# SCH_555.net
KiCad netlist of a schematic drawn in Altium Designer
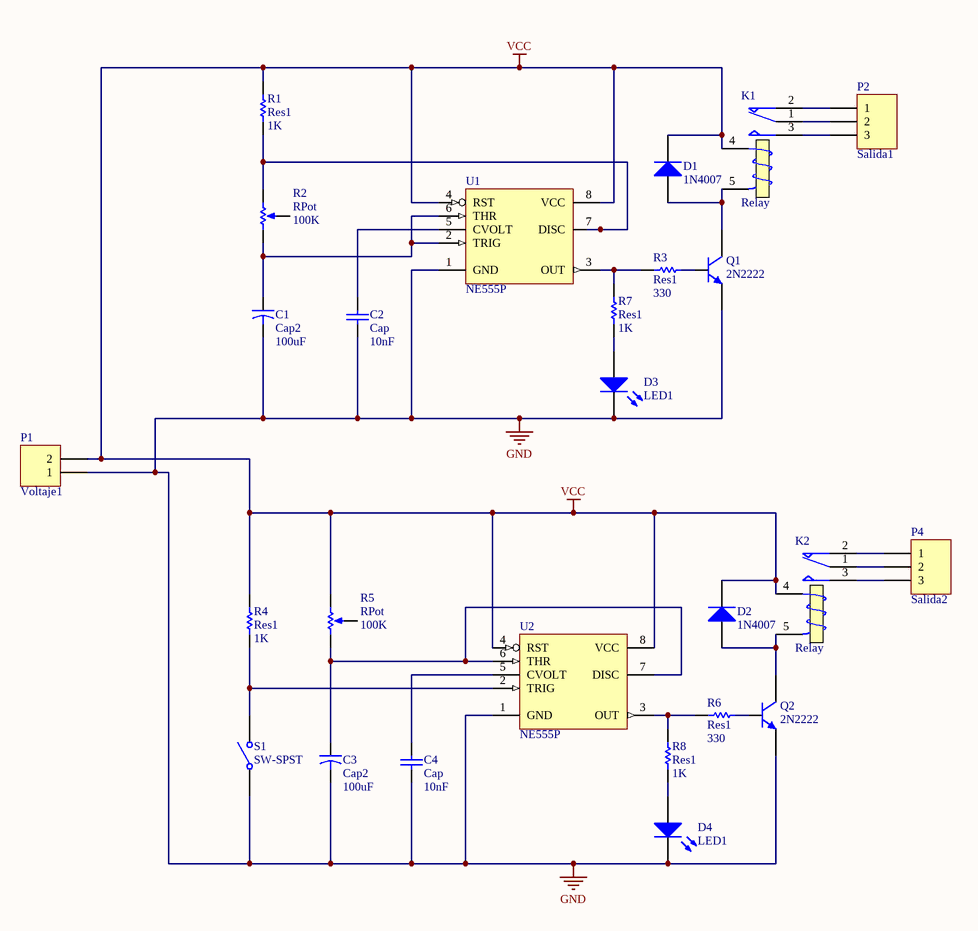
[diagram p0: SCH_555.SchDoc]

(export (version "E")
  (design (tool "Eeschema 10.0.6"))
  (components
    (comp (ref "C1")
      (value "Cap2")
      (footprint "Cap 100uf 25v")
      (description "Capacitor")
      (fields (field (name "ALTIUM_VALUE") "100uF") (field (name "PUBLISHER") "Altium Limited"))
      (libsource (lib "Miscellaneous Devices") (part "Cap2"))
    )
    (comp (ref "C2")
      (value "Cap")
      (footprint "CAP")
      (description "Capacitor")
      (fields (field (name "ALTIUM_VALUE") "10nF") (field (name "PUBLISHER") "Altium Limited"))
      (libsource (lib "Miscellaneous Devices") (part "Cap"))
    )
    (comp (ref "C3")
      (value "Cap2")
      (footprint "Cap 100uf 25v")
      (description "Capacitor")
      (fields (field (name "ALTIUM_VALUE") "100uF") (field (name "PUBLISHER") "Altium Limited"))
      (libsource (lib "Miscellaneous Devices") (part "Cap2"))
    )
    (comp (ref "C4")
      (value "Cap")
      (footprint "CAP")
      (description "Capacitor")
      (fields (field (name "ALTIUM_VALUE") "10nF") (field (name "PUBLISHER") "Altium Limited"))
      (libsource (lib "Miscellaneous Devices") (part "Cap"))
    )
    (comp (ref "D1")
      (value "1N4007")
      (footprint "DO-41")
      (description "1 Amp General Purpose Rectifier")
      (fields (field (name "PUBLISHER") "Altium Limited"))
      (libsource (lib "Miscellaneous Devices") (part "Diode 1N4007"))
    )
    (comp (ref "D2")
      (value "1N4007")
      (footprint "DO-41")
      (description "1 Amp General Purpose Rectifier")
      (fields (field (name "PUBLISHER") "Altium Limited"))
      (libsource (lib "Miscellaneous Devices") (part "Diode 1N4007"))
    )
    (comp (ref "D3")
      (value "LED1")
      (footprint "Cap 100uf 25v")
      (description "Typical RED GaAs LED")
      (fields (field (name "PUBLISHER") "Altium Limited"))
      (libsource (lib "Miscellaneous Devices") (part "LED1"))
    )
    (comp (ref "D4")
      (value "LED1")
      (footprint "Cap 100uf 25v")
      (description "Typical RED GaAs LED")
      (fields (field (name "PUBLISHER") "Altium Limited"))
      (libsource (lib "Miscellaneous Devices") (part "LED1"))
    )
    (comp (ref "K1")
      (value "Relay")
      (footprint "Relay")
      (description "SPDT Relay")
      (fields (field (name "PUBLISHER") "Altium Limited"))
      (libsource (lib "Miscellaneous Devices") (part "Relay"))
    )
    (comp (ref "K2")
      (value "Relay")
      (footprint "Relay")
      (description "SPDT Relay")
      (fields (field (name "PUBLISHER") "Altium Limited"))
      (libsource (lib "Miscellaneous Devices") (part "Relay"))
    )
    (comp (ref "P1")
      (value "Voltaje1")
      (footprint "TErminal")
      (description "Header, 2-Pin")
      (fields (field (name "PUBLISHER") "Altium Limited"))
      (libsource (lib "Miscellaneous Connectors") (part "Header 2"))
    )
    (comp (ref "P2")
      (value "Salida1")
      (footprint "TErminal3")
      (description "Header, 3-Pin")
      (fields (field (name "PUBLISHER") "Altium Limited"))
      (libsource (lib "Miscellaneous Connectors") (part "Header 3"))
    )
    (comp (ref "P4")
      (value "Salida2")
      (footprint "TErminal3")
      (description "Header, 3-Pin")
      (fields (field (name "PUBLISHER") "Altium Limited"))
      (libsource (lib "Miscellaneous Connectors") (part "Header 3"))
    )
    (comp (ref "Q1")
      (value "2N2222")
      (footprint "TO-92A")
      (description "NPN General Purpose Amplifier")
      (fields (field (name "PUBLISHER") "Altium Limited"))
      (libsource (lib "Miscellaneous Devices") (part "2N3904"))
    )
    (comp (ref "Q2")
      (value "2N2222")
      (footprint "TO-92A")
      (description "NPN General Purpose Amplifier")
      (fields (field (name "PUBLISHER") "Altium Limited"))
      (libsource (lib "Miscellaneous Devices") (part "2N3904"))
    )
    (comp (ref "R1")
      (value "Res1")
      (footprint "AXIAL-0.3")
      (description "Resistor")
      (fields (field (name "ALTIUM_VALUE") "1K") (field (name "PUBLISHER") "Altium Limited"))
      (libsource (lib "Miscellaneous Devices") (part "Res1"))
    )
    (comp (ref "R2")
      (value "RPot")
      (footprint "Potenciometro")
      (description "Potentiometer")
      (fields (field (name "ALTIUM_VALUE") "100K") (field (name "PUBLISHER") "Altium Limited"))
      (libsource (lib "Miscellaneous Devices") (part "RPot"))
    )
    (comp (ref "R3")
      (value "Res1")
      (footprint "AXIAL-0.3")
      (description "Resistor")
      (fields (field (name "ALTIUM_VALUE") "330") (field (name "PUBLISHER") "Altium Limited"))
      (libsource (lib "Miscellaneous Devices") (part "Res1"))
    )
    (comp (ref "R4")
      (value "Res1")
      (footprint "AXIAL-0.3")
      (description "Resistor")
      (fields (field (name "ALTIUM_VALUE") "1K") (field (name "PUBLISHER") "Altium Limited"))
      (libsource (lib "Miscellaneous Devices") (part "Res1"))
    )
    (comp (ref "R5")
      (value "RPot")
      (footprint "Potenciometro")
      (description "Potentiometer")
      (fields (field (name "ALTIUM_VALUE") "100K") (field (name "PUBLISHER") "Altium Limited"))
      (libsource (lib "Miscellaneous Devices") (part "RPot"))
    )
    (comp (ref "R6")
      (value "Res1")
      (footprint "AXIAL-0.3")
      (description "Resistor")
      (fields (field (name "ALTIUM_VALUE") "330") (field (name "PUBLISHER") "Altium Limited"))
      (libsource (lib "Miscellaneous Devices") (part "Res1"))
    )
    (comp (ref "R7")
      (value "Res1")
      (footprint "AXIAL-0.3")
      (description "Resistor")
      (fields (field (name "ALTIUM_VALUE") "1K") (field (name "PUBLISHER") "Altium Limited"))
      (libsource (lib "Miscellaneous Devices") (part "Res1"))
    )
    (comp (ref "R8")
      (value "Res1")
      (footprint "AXIAL-0.3")
      (description "Resistor")
      (fields (field (name "ALTIUM_VALUE") "1K") (field (name "PUBLISHER") "Altium Limited"))
      (libsource (lib "Miscellaneous Devices") (part "Res1"))
    )
    (comp (ref "S1")
      (value "SW-SPST")
      (footprint "PUSHB")
      (description "Single-Pole, Single-Throw Switch")
      (fields (field (name "PUBLISHER") "Altium Limited"))
      (libsource (lib "Miscellaneous Devices") (part "SW-SPST"))
    )
    (comp (ref "U1")
      (value "NE555P")
      (footprint "P008")
      (description "Precision Timer")
      (fields (field (name "PUBLISHER") "Altium Limited"))
      (libsource (lib "TI Analog Timer Circuit") (part "NE555P"))
    )
    (comp (ref "U2")
      (value "NE555P")
      (footprint "P008")
      (description "Precision Timer")
      (fields (field (name "PUBLISHER") "Altium Limited"))
      (libsource (lib "TI Analog Timer Circuit") (part "NE555P"))
    )
  )
  (nets
    (net (code "1") (name "GND") (class "Default")
      (node (ref "C1") (pin "2") (pinfunction "2_2") (pintype "passive"))
      (node (ref "C2") (pin "1") (pinfunction "1_1") (pintype "passive"))
      (node (ref "C3") (pin "2") (pinfunction "2_2") (pintype "passive"))
      (node (ref "C4") (pin "1") (pinfunction "1_1") (pintype "passive"))
      (node (ref "D3") (pin "2") (pinfunction "K_2") (pintype "passive"))
      (node (ref "D4") (pin "2") (pinfunction "K_2") (pintype "passive"))
      (node (ref "P1") (pin "1") (pinfunction "1_1") (pintype "passive"))
      (node (ref "Q1") (pin "1") (pinfunction "E_1") (pintype "passive"))
      (node (ref "Q2") (pin "1") (pinfunction "E_1") (pintype "passive"))
      (node (ref "S1") (pin "1") (pinfunction "COMMON_1") (pintype "passive"))
      (node (ref "U1") (pin "1") (pinfunction "GND_1") (pintype "power_in"))
      (node (ref "U2") (pin "1") (pinfunction "GND_1") (pintype "power_in"))
    )
    (net (code "2") (name "Net-(D1-A)") (class "Default")
      (node (ref "D1") (pin "1") (pinfunction "A_1") (pintype "passive"))
      (node (ref "K1") (pin "5") (pinfunction "T2_5") (pintype "passive"))
      (node (ref "Q1") (pin "3") (pinfunction "C_3") (pintype "passive"))
    )
    (net (code "3") (name "Net-(D2-A)") (class "Default")
      (node (ref "D2") (pin "1") (pinfunction "A_1") (pintype "passive"))
      (node (ref "K2") (pin "5") (pinfunction "T2_5") (pintype "passive"))
      (node (ref "Q2") (pin "3") (pinfunction "C_3") (pintype "passive"))
    )
    (net (code "4") (name "Net-(D3-A)") (class "Default")
      (node (ref "D3") (pin "1") (pinfunction "A_1") (pintype "passive"))
      (node (ref "R7") (pin "1") (pinfunction "1_1") (pintype "passive"))
    )
    (net (code "5") (name "Net-(D4-A)") (class "Default")
      (node (ref "D4") (pin "1") (pinfunction "A_1") (pintype "passive"))
      (node (ref "R8") (pin "1") (pinfunction "1_1") (pintype "passive"))
    )
    (net (code "6") (name "Net-(K1-COM)") (class "Default")
      (node (ref "K1") (pin "1") (pinfunction "COM_1") (pintype "passive"))
      (node (ref "P2") (pin "2") (pinfunction "2_2") (pintype "passive"))
    )
    (net (code "7") (name "Net-(K1-NC)") (class "Default")
      (node (ref "K1") (pin "2") (pinfunction "NC_2") (pintype "passive"))
      (node (ref "P2") (pin "1") (pinfunction "1_1") (pintype "passive"))
    )
    (net (code "8") (name "Net-(K1-NO)") (class "Default")
      (node (ref "K1") (pin "3") (pinfunction "NO_3") (pintype "passive"))
      (node (ref "P2") (pin "3") (pinfunction "3_3") (pintype "passive"))
    )
    (net (code "9") (name "Net-(K2-COM)") (class "Default")
      (node (ref "K2") (pin "1") (pinfunction "COM_1") (pintype "passive"))
      (node (ref "P4") (pin "2") (pinfunction "2_2") (pintype "passive"))
    )
    (net (code "10") (name "Net-(K2-NC)") (class "Default")
      (node (ref "K2") (pin "2") (pinfunction "NC_2") (pintype "passive"))
      (node (ref "P4") (pin "1") (pinfunction "1_1") (pintype "passive"))
    )
    (net (code "11") (name "Net-(K2-NO)") (class "Default")
      (node (ref "K2") (pin "3") (pinfunction "NO_3") (pintype "passive"))
      (node (ref "P4") (pin "3") (pinfunction "3_3") (pintype "passive"))
    )
    (net (code "12") (name "Net-(Q1-B)") (class "Default")
      (node (ref "Q1") (pin "2") (pinfunction "B_2") (pintype "passive"))
      (node (ref "R3") (pin "2") (pinfunction "2_2") (pintype "passive"))
    )
    (net (code "13") (name "Net-(Q2-B)") (class "Default")
      (node (ref "Q2") (pin "2") (pinfunction "B_2") (pintype "passive"))
      (node (ref "R6") (pin "2") (pinfunction "2_2") (pintype "passive"))
    )
    (net (code "14") (name "Net-(R2-BOT)") (class "Default")
      (node (ref "R1") (pin "1") (pinfunction "1_1") (pintype "passive"))
      (node (ref "R2") (pin "2") (pinfunction "BOT_2") (pintype "passive"))
      (node (ref "U1") (pin "7") (pinfunction "DISC_7") (pintype "open_collector"))
    )
    (net (code "15") (name "Net-(R2-TOP)") (class "Default")
      (node (ref "C1") (pin "1") (pinfunction "1_1") (pintype "passive"))
      (node (ref "R2") (pin "1") (pinfunction "TOP_1") (pintype "passive"))
      (node (ref "U1") (pin "2") (pinfunction "TRIG_2") (pintype "input"))
      (node (ref "U1") (pin "6") (pinfunction "THR_6") (pintype "input"))
    )
    (net (code "16") (name "Net-(R5-TOP)") (class "Default")
      (node (ref "C3") (pin "1") (pinfunction "1_1") (pintype "passive"))
      (node (ref "R5") (pin "1") (pinfunction "TOP_1") (pintype "passive"))
      (node (ref "U2") (pin "6") (pinfunction "THR_6") (pintype "input"))
      (node (ref "U2") (pin "7") (pinfunction "DISC_7") (pintype "open_collector"))
    )
    (net (code "17") (name "Net-(S1-NO)") (class "Default")
      (node (ref "R4") (pin "1") (pinfunction "1_1") (pintype "passive"))
      (node (ref "S1") (pin "2") (pinfunction "NO_2") (pintype "passive"))
      (node (ref "U2") (pin "2") (pinfunction "TRIG_2") (pintype "input"))
    )
    (net (code "18") (name "Net-(U1-CVOLT)") (class "Default")
      (node (ref "C2") (pin "2") (pinfunction "2_2") (pintype "passive"))
      (node (ref "U1") (pin "5") (pinfunction "CVOLT_5") (pintype "passive"))
    )
    (net (code "19") (name "Net-(U1-OUT)") (class "Default")
      (node (ref "R3") (pin "1") (pinfunction "1_1") (pintype "passive"))
      (node (ref "R7") (pin "2") (pinfunction "2_2") (pintype "passive"))
      (node (ref "U1") (pin "3") (pinfunction "OUT_3") (pintype "output"))
    )
    (net (code "20") (name "Net-(U2-CVOLT)") (class "Default")
      (node (ref "C4") (pin "2") (pinfunction "2_2") (pintype "passive"))
      (node (ref "U2") (pin "5") (pinfunction "CVOLT_5") (pintype "passive"))
    )
    (net (code "21") (name "Net-(U2-OUT)") (class "Default")
      (node (ref "R6") (pin "1") (pinfunction "1_1") (pintype "passive"))
      (node (ref "R8") (pin "2") (pinfunction "2_2") (pintype "passive"))
      (node (ref "U2") (pin "3") (pinfunction "OUT_3") (pintype "output"))
    )
    (net (code "22") (name "VCC") (class "Default")
      (node (ref "D1") (pin "2") (pinfunction "K_2") (pintype "passive"))
      (node (ref "D2") (pin "2") (pinfunction "K_2") (pintype "passive"))
      (node (ref "K1") (pin "4") (pinfunction "T1_4") (pintype "passive"))
      (node (ref "K2") (pin "4") (pinfunction "T1_4") (pintype "passive"))
      (node (ref "P1") (pin "2") (pinfunction "2_2") (pintype "passive"))
      (node (ref "R1") (pin "2") (pinfunction "2_2") (pintype "passive"))
      (node (ref "R4") (pin "2") (pinfunction "2_2") (pintype "passive"))
      (node (ref "R5") (pin "2") (pinfunction "BOT_2") (pintype "passive"))
      (node (ref "U1") (pin "4") (pinfunction "RST_4") (pintype "input"))
      (node (ref "U1") (pin "8") (pinfunction "VCC_8") (pintype "power_in"))
      (node (ref "U2") (pin "4") (pinfunction "RST_4") (pintype "input"))
      (node (ref "U2") (pin "8") (pinfunction "VCC_8") (pintype "power_in"))
    )
    (net (code "23") (name "unconnected-(R2-TAP-Pad3)") (class "Default")
      (node (ref "R2") (pin "3") (pinfunction "TAP_3") (pintype "passive"))
    )
    (net (code "24") (name "unconnected-(R5-TAP-Pad3)") (class "Default")
      (node (ref "R5") (pin "3") (pinfunction "TAP_3") (pintype "passive"))
    )
  )
)
